# backfin_wifi.net
KiCad netlist of a schematic drawn in EAGLE
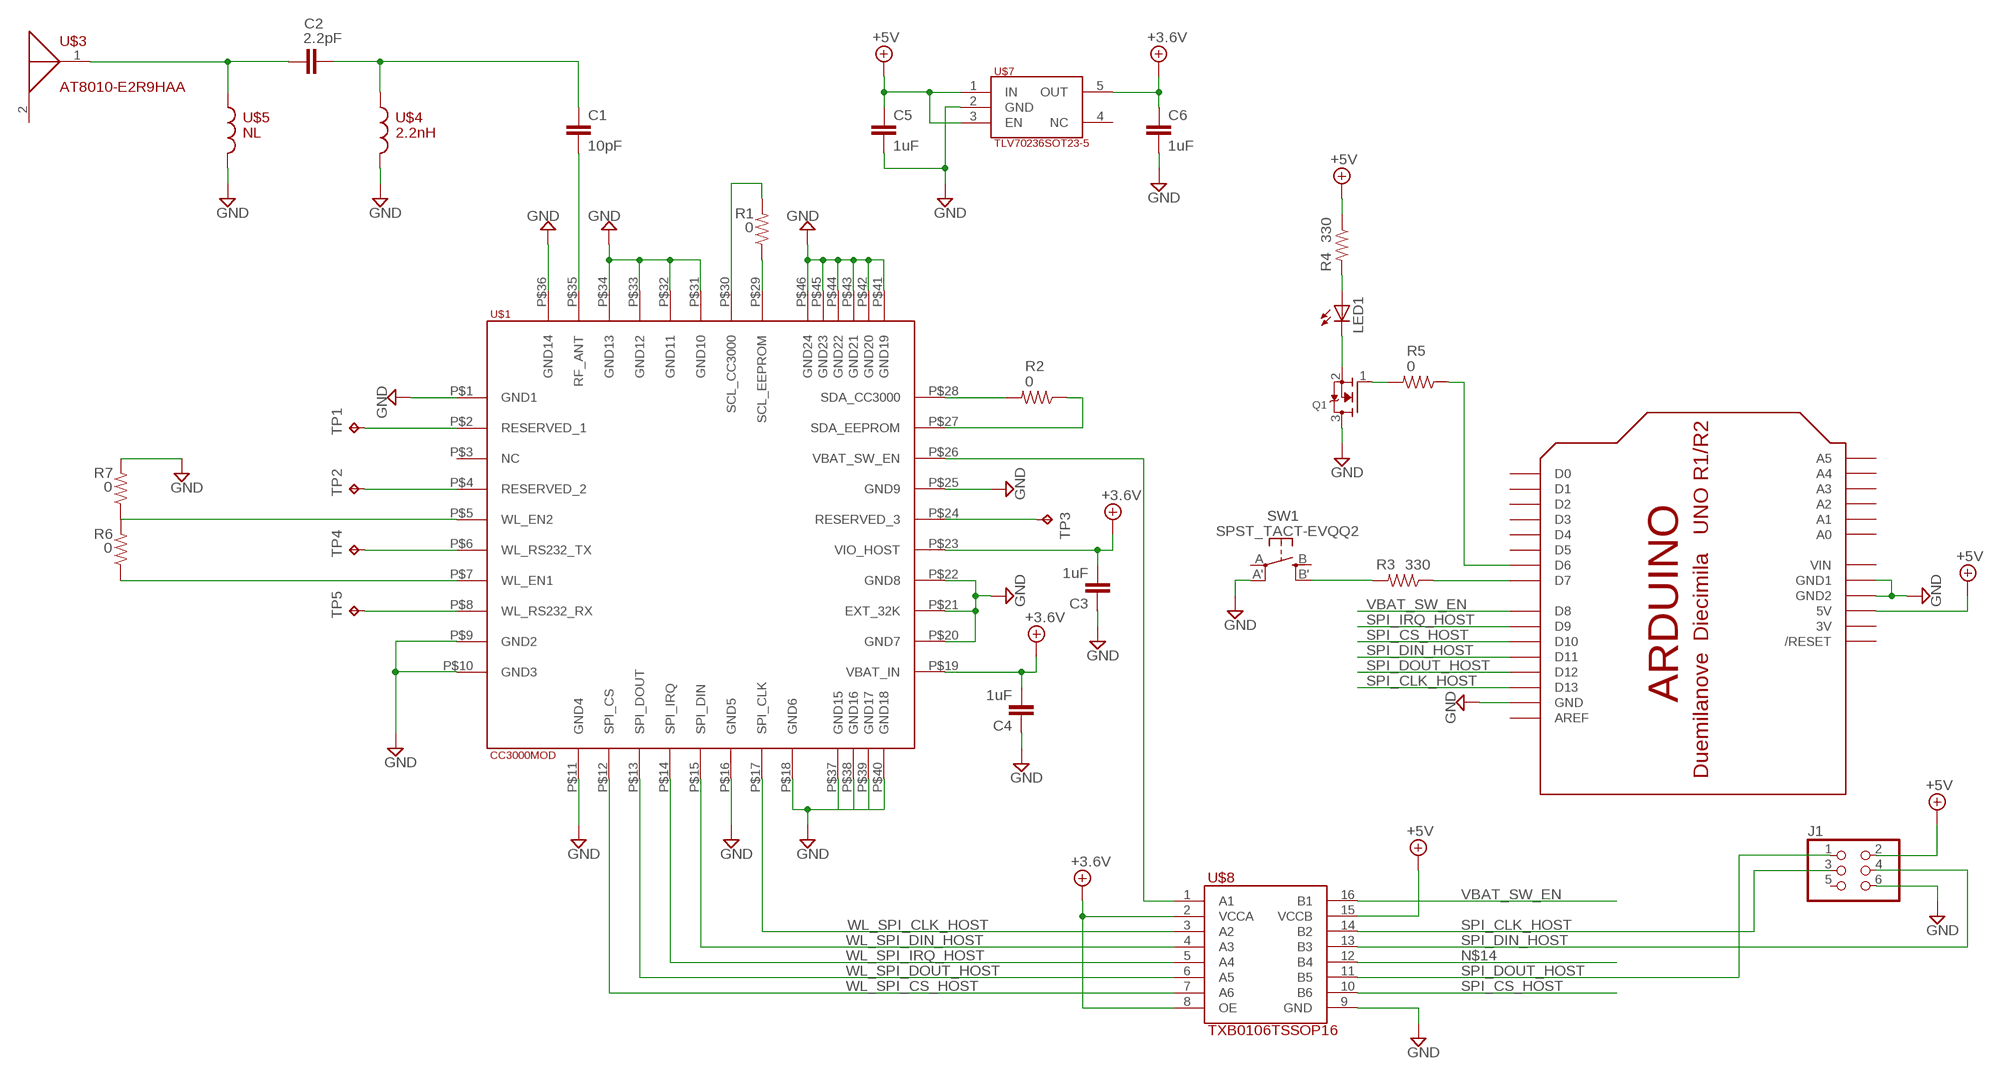
[diagram p0: schematic, sheet 1]

(export (version "E")
  (design (tool "Eeschema 10.0.6"))
  (components
    (comp (ref "C1")
      (value "10pF")
      (footprint "eagle-import:C0402K")
      (libsource (lib "eagle-import") (part "C-EUC0402K"))
    )
    (comp (ref "C2")
      (value "2.2pF")
      (footprint "eagle-import:C0402K")
      (libsource (lib "eagle-import") (part "C-EUC0402K"))
    )
    (comp (ref "C3")
      (value "1uF")
      (footprint "eagle-import:C0402K")
      (libsource (lib "eagle-import") (part "C-EUC0402K"))
    )
    (comp (ref "C4")
      (value "1uF")
      (footprint "eagle-import:C0402K")
      (libsource (lib "eagle-import") (part "C-EUC0402K"))
    )
    (comp (ref "C5")
      (value "1uF")
      (footprint "eagle-import:C0402K")
      (libsource (lib "eagle-import") (part "resistor_C-EUC0402K"))
    )
    (comp (ref "C6")
      (value "1uF")
      (footprint "eagle-import:C0402K")
      (libsource (lib "eagle-import") (part "resistor_C-EUC0402K"))
    )
    (comp (ref "J1")
      (value "PINHD-2X3")
      (footprint "eagle-import:2X03")
      (libsource (lib "eagle-import") (part "PINHD-2X3"))
    )
    (comp (ref "LED1")
      (value "LEDCHIPLED_1206")
      (footprint "eagle-import:CHIPLED_1206")
      (libsource (lib "eagle-import") (part "LEDCHIPLED_1206"))
    )
    (comp (ref "Q1")
      (value "MOSFET-NREFLOW")
      (footprint "eagle-import:SOT23")
      (libsource (lib "eagle-import") (part "MOSFET-NREFLOW"))
    )
    (comp (ref "R1")
      (value "0")
      (footprint "eagle-import:R1005")
      (libsource (lib "eagle-import") (part "R-US_R1005"))
    )
    (comp (ref "R2")
      (value "0")
      (footprint "eagle-import:R1005")
      (libsource (lib "eagle-import") (part "R-US_R1005"))
    )
    (comp (ref "R3")
      (value "330")
      (footprint "eagle-import:R1005")
      (libsource (lib "eagle-import") (part "R-US_R1005"))
    )
    (comp (ref "R4")
      (value "330")
      (footprint "eagle-import:R1005")
      (libsource (lib "eagle-import") (part "R-US_R1005"))
    )
    (comp (ref "R5")
      (value "0")
      (footprint "eagle-import:R1005")
      (libsource (lib "eagle-import") (part "R-US_R1005"))
    )
    (comp (ref "R6")
      (value "0")
      (footprint "eagle-import:R1005")
      (libsource (lib "eagle-import") (part "R-US_R1005"))
    )
    (comp (ref "R7")
      (value "0")
      (footprint "eagle-import:R1005")
      (libsource (lib "eagle-import") (part "R-US_R1005"))
    )
    (comp (ref "SW1")
      (value "SPST_TACT-EVQQ2")
      (footprint "eagle-import:EVQ-Q2")
      (libsource (lib "eagle-import") (part "SPST_TACT-EVQQ2"))
    )
    (comp (ref "TP1")
      (value "TPPAD1-13")
      (footprint "eagle-import:P1-13")
      (libsource (lib "eagle-import") (part "TPPAD1-13"))
    )
    (comp (ref "TP2")
      (value "TPPAD1-13")
      (footprint "eagle-import:P1-13")
      (libsource (lib "eagle-import") (part "TPPAD1-13"))
    )
    (comp (ref "TP3")
      (value "TPPAD1-13")
      (footprint "eagle-import:P1-13")
      (libsource (lib "eagle-import") (part "TPPAD1-13"))
    )
    (comp (ref "TP4")
      (value "TPPAD1-13")
      (footprint "eagle-import:P1-13")
      (libsource (lib "eagle-import") (part "TPPAD1-13"))
    )
    (comp (ref "TP5")
      (value "TPPAD1-13")
      (footprint "eagle-import:P1-13")
      (libsource (lib "eagle-import") (part "TPPAD1-13"))
    )
    (comp (ref "U$1")
      (value "CC3000MOD")
      (footprint "eagle-import:CC3000MOD")
      (libsource (lib "eagle-import") (part "CC3000MOD"))
    )
    (comp (ref "U$2")
      (value "ARDUINOUNO")
      (footprint "eagle-import:ARDUINO")
      (libsource (lib "eagle-import") (part "ARDUINOUNO"))
    )
    (comp (ref "U$3")
      (value "AT8010-E2R9HAA")
      (footprint "eagle-import:AT8010-E2R9HAA")
      (libsource (lib "eagle-import") (part "AT8010-E2R9HAA"))
    )
    (comp (ref "U$4")
      (value "2.2nH")
      (footprint "eagle-import:0402")
      (libsource (lib "eagle-import") (part "INDUCTOR"))
    )
    (comp (ref "U$5")
      (value "NL")
      (footprint "eagle-import:0402")
      (libsource (lib "eagle-import") (part "INDUCTOR"))
    )
    (comp (ref "U$7")
      (value "TLV70236SOT23-5")
      (footprint "eagle-import:SOT23-DBV")
      (libsource (lib "eagle-import") (part "TLV70236SOT23-5"))
    )
    (comp (ref "U$8")
      (value "TXB0106TSSOP16")
      (footprint "eagle-import:TSSOP16")
      (libsource (lib "eagle-import") (part "TXB0106TSSOP16"))
    )
  )
  (nets
    (net (code "1") (name "+3.6V") (class "Default")
      (node (ref "C3") (pin "2") (pinfunction "2_2") (pintype "passive"))
      (node (ref "C4") (pin "2") (pinfunction "2_2") (pintype "passive"))
      (node (ref "C6") (pin "1") (pinfunction "1_1") (pintype "passive"))
      (node (ref "U$1") (pin "P$19") (pinfunction "VBAT_IN_P$19") (pintype "bidirectional"))
      (node (ref "U$1") (pin "P$23") (pinfunction "VIO_HOST_P$23") (pintype "bidirectional"))
      (node (ref "U$7") (pin "5") (pinfunction "OUT_5") (pintype "bidirectional"))
      (node (ref "U$8") (pin "2") (pinfunction "VCCA_2") (pintype "bidirectional"))
      (node (ref "U$8") (pin "8") (pinfunction "OE_8") (pintype "bidirectional"))
    )
    (net (code "2") (name "+5V") (class "Default")
      (node (ref "C5") (pin "1") (pinfunction "1_1") (pintype "passive"))
      (node (ref "J1") (pin "2") (pinfunction "2_2") (pintype "passive"))
      (node (ref "R4") (pin "1") (pinfunction "1_1") (pintype "passive"))
      (node (ref "U$2") (pin "5V") (pinfunction "5V_5V") (pintype "power_in"))
      (node (ref "U$7") (pin "1") (pinfunction "IN_1") (pintype "bidirectional"))
      (node (ref "U$7") (pin "3") (pinfunction "EN_3") (pintype "bidirectional"))
      (node (ref "U$8") (pin "15") (pinfunction "VCCB_15") (pintype "bidirectional"))
    )
    (net (code "3") (name "/3V") (class "Default")
      (node (ref "U$2") (pin "3V") (pinfunction "3V_3V") (pintype "power_in"))
    )
    (net (code "4") (name "/N$14") (class "Default")
      (node (ref "U$8") (pin "12") (pinfunction "B4_12") (pintype "bidirectional"))
    )
    (net (code "5") (name "/SPI_CLK_HOST") (class "Default")
      (node (ref "J1") (pin "3") (pinfunction "3_3") (pintype "passive"))
      (node (ref "U$2") (pin "D13") (pinfunction "D13_D13") (pintype "bidirectional"))
      (node (ref "U$8") (pin "14") (pinfunction "B2_14") (pintype "bidirectional"))
    )
    (net (code "6") (name "/SPI_CS_HOST") (class "Default")
      (node (ref "U$2") (pin "D10") (pinfunction "D10_D10") (pintype "bidirectional"))
      (node (ref "U$8") (pin "10") (pinfunction "B6_10") (pintype "bidirectional"))
    )
    (net (code "7") (name "/SPI_DIN_HOST") (class "Default")
      (node (ref "J1") (pin "4") (pinfunction "4_4") (pintype "passive"))
      (node (ref "U$2") (pin "D11") (pinfunction "D11_D11") (pintype "bidirectional"))
      (node (ref "U$8") (pin "13") (pinfunction "B3_13") (pintype "bidirectional"))
    )
    (net (code "8") (name "/SPI_DOUT_HOST") (class "Default")
      (node (ref "J1") (pin "1") (pinfunction "1_1") (pintype "passive"))
      (node (ref "U$2") (pin "D12") (pinfunction "D12_D12") (pintype "bidirectional"))
      (node (ref "U$8") (pin "11") (pinfunction "B5_11") (pintype "bidirectional"))
    )
    (net (code "9") (name "/SPI_IRQ_HOST") (class "Default")
      (node (ref "U$2") (pin "D9") (pinfunction "D9_D9") (pintype "bidirectional"))
    )
    (net (code "10") (name "/VBAT_SW_EN") (class "Default")
      (node (ref "U$2") (pin "D8") (pinfunction "D8_D8") (pintype "bidirectional"))
      (node (ref "U$8") (pin "16") (pinfunction "B1_16") (pintype "bidirectional"))
    )
    (net (code "11") (name "/VIN") (class "Default")
      (node (ref "U$2") (pin "VIN") (pinfunction "VIN_VIN") (pintype "power_in"))
    )
    (net (code "12") (name "/WL_SPI_CLK_HOST") (class "Default")
      (node (ref "U$1") (pin "P$17") (pinfunction "SPI_CLK_P$17") (pintype "bidirectional"))
      (node (ref "U$8") (pin "3") (pinfunction "A2_3") (pintype "bidirectional"))
    )
    (net (code "13") (name "/WL_SPI_CS_HOST") (class "Default")
      (node (ref "U$1") (pin "P$12") (pinfunction "SPI_CS_P$12") (pintype "bidirectional"))
      (node (ref "U$8") (pin "7") (pinfunction "A6_7") (pintype "bidirectional"))
    )
    (net (code "14") (name "/WL_SPI_DIN_HOST") (class "Default")
      (node (ref "U$1") (pin "P$15") (pinfunction "SPI_DIN_P$15") (pintype "bidirectional"))
      (node (ref "U$8") (pin "4") (pinfunction "A3_4") (pintype "bidirectional"))
    )
    (net (code "15") (name "/WL_SPI_DOUT_HOST") (class "Default")
      (node (ref "U$1") (pin "P$13") (pinfunction "SPI_DOUT_P$13") (pintype "bidirectional"))
      (node (ref "U$8") (pin "6") (pinfunction "A5_6") (pintype "bidirectional"))
    )
    (net (code "16") (name "/WL_SPI_IRQ_HOST") (class "Default")
      (node (ref "U$1") (pin "P$14") (pinfunction "SPI_IRQ_P$14") (pintype "bidirectional"))
      (node (ref "U$8") (pin "5") (pinfunction "A4_5") (pintype "bidirectional"))
    )
    (net (code "17") (name "GND") (class "Default")
      (node (ref "C3") (pin "1") (pinfunction "1_1") (pintype "passive"))
      (node (ref "C4") (pin "1") (pinfunction "1_1") (pintype "passive"))
      (node (ref "C5") (pin "2") (pinfunction "2_2") (pintype "passive"))
      (node (ref "C6") (pin "2") (pinfunction "2_2") (pintype "passive"))
      (node (ref "J1") (pin "6") (pinfunction "6_6") (pintype "passive"))
      (node (ref "Q1") (pin "3") (pinfunction "D_3") (pintype "bidirectional"))
      (node (ref "R7") (pin "2") (pinfunction "2_2") (pintype "passive"))
      (node (ref "SW1") (pin "A'") (pinfunction "P1_A'") (pintype "passive"))
      (node (ref "U$1") (pin "P$1") (pinfunction "GND1_P$1") (pintype "bidirectional"))
      (node (ref "U$1") (pin "P$10") (pinfunction "GND3_P$10") (pintype "bidirectional"))
      (node (ref "U$1") (pin "P$11") (pinfunction "GND4_P$11") (pintype "bidirectional"))
      (node (ref "U$1") (pin "P$16") (pinfunction "GND5_P$16") (pintype "bidirectional"))
      (node (ref "U$1") (pin "P$18") (pinfunction "GND6_P$18") (pintype "bidirectional"))
      (node (ref "U$1") (pin "P$20") (pinfunction "GND7_P$20") (pintype "bidirectional"))
      (node (ref "U$1") (pin "P$21") (pinfunction "EXT_32K_P$21") (pintype "bidirectional"))
      (node (ref "U$1") (pin "P$22") (pinfunction "GND8_P$22") (pintype "bidirectional"))
      (node (ref "U$1") (pin "P$25") (pinfunction "GND9_P$25") (pintype "bidirectional"))
      (node (ref "U$1") (pin "P$31") (pinfunction "GND10_P$31") (pintype "bidirectional"))
      (node (ref "U$1") (pin "P$32") (pinfunction "GND11_P$32") (pintype "bidirectional"))
      (node (ref "U$1") (pin "P$33") (pinfunction "GND12_P$33") (pintype "bidirectional"))
      (node (ref "U$1") (pin "P$34") (pinfunction "GND13_P$34") (pintype "bidirectional"))
      (node (ref "U$1") (pin "P$36") (pinfunction "GND14_P$36") (pintype "bidirectional"))
      (node (ref "U$1") (pin "P$37") (pinfunction "GND15_P$37") (pintype "bidirectional"))
      (node (ref "U$1") (pin "P$38") (pinfunction "GND16_P$38") (pintype "bidirectional"))
      (node (ref "U$1") (pin "P$39") (pinfunction "GND17_P$39") (pintype "bidirectional"))
      (node (ref "U$1") (pin "P$40") (pinfunction "GND18_P$40") (pintype "bidirectional"))
      (node (ref "U$1") (pin "P$41") (pinfunction "GND19_P$41") (pintype "bidirectional"))
      (node (ref "U$1") (pin "P$42") (pinfunction "GND20_P$42") (pintype "bidirectional"))
      (node (ref "U$1") (pin "P$43") (pinfunction "GND21_P$43") (pintype "bidirectional"))
      (node (ref "U$1") (pin "P$44") (pinfunction "GND22_P$44") (pintype "bidirectional"))
      (node (ref "U$1") (pin "P$45") (pinfunction "GND23_P$45") (pintype "bidirectional"))
      (node (ref "U$1") (pin "P$46") (pinfunction "GND24_P$46") (pintype "bidirectional"))
      (node (ref "U$1") (pin "P$9") (pinfunction "GND2_P$9") (pintype "bidirectional"))
      (node (ref "U$2") (pin "GND") (pinfunction "GND_GND") (pintype "power_in"))
      (node (ref "U$2") (pin "GND1") (pinfunction "GND1_GND1") (pintype "power_in"))
      (node (ref "U$2") (pin "GND2") (pinfunction "GND2_GND2") (pintype "power_in"))
      (node (ref "U$4") (pin "2") (pinfunction "2_2") (pintype "bidirectional"))
      (node (ref "U$5") (pin "2") (pinfunction "2_2") (pintype "bidirectional"))
      (node (ref "U$7") (pin "2") (pinfunction "GND_2") (pintype "bidirectional"))
      (node (ref "U$8") (pin "9") (pinfunction "GND_9") (pintype "bidirectional"))
    )
    (net (code "18") (name "Net-(C1-Pad1)") (class "Default")
      (node (ref "C1") (pin "1") (pinfunction "1_1") (pintype "passive"))
      (node (ref "C2") (pin "2") (pinfunction "2_2") (pintype "passive"))
      (node (ref "U$4") (pin "1") (pinfunction "1_1") (pintype "bidirectional"))
    )
    (net (code "19") (name "Net-(LED1-PadA)") (class "Default")
      (node (ref "LED1") (pin "A") (pinfunction "A_A") (pintype "passive"))
      (node (ref "R4") (pin "2") (pinfunction "2_2") (pintype "passive"))
    )
    (net (code "20") (name "Net-(Q1-G)") (class "Default")
      (node (ref "Q1") (pin "1") (pinfunction "G_1") (pintype "bidirectional"))
      (node (ref "R5") (pin "2") (pinfunction "2_2") (pintype "passive"))
    )
    (net (code "21") (name "Net-(Q1-S)") (class "Default")
      (node (ref "LED1") (pin "C") (pinfunction "C_C") (pintype "passive"))
      (node (ref "Q1") (pin "2") (pinfunction "S_2") (pintype "bidirectional"))
    )
    (net (code "22") (name "Net-(R3-Pad1)") (class "Default")
      (node (ref "R3") (pin "1") (pinfunction "1_1") (pintype "passive"))
      (node (ref "U$2") (pin "D7") (pinfunction "D7_D7") (pintype "bidirectional"))
    )
    (net (code "23") (name "Net-(R5-Pad1)") (class "Default")
      (node (ref "R5") (pin "1") (pinfunction "1_1") (pintype "passive"))
      (node (ref "U$2") (pin "D6") (pinfunction "D6_D6") (pintype "bidirectional"))
    )
    (net (code "24") (name "Net-(SW1-S1)") (class "Default")
      (node (ref "R3") (pin "2") (pinfunction "2_2") (pintype "passive"))
      (node (ref "SW1") (pin "B'") (pinfunction "S1_B'") (pintype "passive"))
    )
    (net (code "25") (name "Net-(U$1-RESERVED_1)") (class "Default")
      (node (ref "TP1") (pin "TP") (pinfunction "TP_TP") (pintype "input"))
      (node (ref "U$1") (pin "P$2") (pinfunction "RESERVED_1_P$2") (pintype "bidirectional"))
    )
    (net (code "26") (name "Net-(U$1-RESERVED_2)") (class "Default")
      (node (ref "TP2") (pin "TP") (pinfunction "TP_TP") (pintype "input"))
      (node (ref "U$1") (pin "P$4") (pinfunction "RESERVED_2_P$4") (pintype "bidirectional"))
    )
    (net (code "27") (name "Net-(U$1-RESERVED_3)") (class "Default")
      (node (ref "TP3") (pin "TP") (pinfunction "TP_TP") (pintype "input"))
      (node (ref "U$1") (pin "P$24") (pinfunction "RESERVED_3_P$24") (pintype "bidirectional"))
    )
    (net (code "28") (name "Net-(U$1-RF_ANT)") (class "Default")
      (node (ref "C1") (pin "2") (pinfunction "2_2") (pintype "passive"))
      (node (ref "U$1") (pin "P$35") (pinfunction "RF_ANT_P$35") (pintype "bidirectional"))
    )
    (net (code "29") (name "Net-(U$1-SCL_CC3000)") (class "Default")
      (node (ref "R1") (pin "2") (pinfunction "2_2") (pintype "passive"))
      (node (ref "U$1") (pin "P$30") (pinfunction "SCL_CC3000_P$30") (pintype "bidirectional"))
    )
    (net (code "30") (name "Net-(U$1-SCL_EEPROM)") (class "Default")
      (node (ref "R1") (pin "1") (pinfunction "1_1") (pintype "passive"))
      (node (ref "U$1") (pin "P$29") (pinfunction "SCL_EEPROM_P$29") (pintype "bidirectional"))
    )
    (net (code "31") (name "Net-(U$1-SDA_CC3000)") (class "Default")
      (node (ref "R2") (pin "2") (pinfunction "2_2") (pintype "passive"))
      (node (ref "U$1") (pin "P$28") (pinfunction "SDA_CC3000_P$28") (pintype "bidirectional"))
    )
    (net (code "32") (name "Net-(U$1-SDA_EEPROM)") (class "Default")
      (node (ref "R2") (pin "1") (pinfunction "1_1") (pintype "passive"))
      (node (ref "U$1") (pin "P$27") (pinfunction "SDA_EEPROM_P$27") (pintype "bidirectional"))
    )
    (net (code "33") (name "Net-(U$1-VBAT_SW_EN)") (class "Default")
      (node (ref "U$1") (pin "P$26") (pinfunction "VBAT_SW_EN_P$26") (pintype "bidirectional"))
      (node (ref "U$8") (pin "1") (pinfunction "A1_1") (pintype "bidirectional"))
    )
    (net (code "34") (name "Net-(U$1-WL_EN1)") (class "Default")
      (node (ref "R6") (pin "1") (pinfunction "1_1") (pintype "passive"))
      (node (ref "U$1") (pin "P$7") (pinfunction "WL_EN1_P$7") (pintype "bidirectional"))
    )
    (net (code "35") (name "Net-(U$1-WL_EN2)") (class "Default")
      (node (ref "R6") (pin "2") (pinfunction "2_2") (pintype "passive"))
      (node (ref "R7") (pin "1") (pinfunction "1_1") (pintype "passive"))
      (node (ref "U$1") (pin "P$5") (pinfunction "WL_EN2_P$5") (pintype "bidirectional"))
    )
    (net (code "36") (name "Net-(U$1-WL_RS232_RX)") (class "Default")
      (node (ref "TP5") (pin "TP") (pinfunction "TP_TP") (pintype "input"))
      (node (ref "U$1") (pin "P$8") (pinfunction "WL_RS232_RX_P$8") (pintype "bidirectional"))
    )
    (net (code "37") (name "Net-(U$1-WL_RS232_TX)") (class "Default")
      (node (ref "TP4") (pin "TP") (pinfunction "TP_TP") (pintype "input"))
      (node (ref "U$1") (pin "P$6") (pinfunction "WL_RS232_TX_P$6") (pintype "bidirectional"))
    )
    (net (code "38") (name "Net-(U$3-FEED)") (class "Default")
      (node (ref "C2") (pin "1") (pinfunction "1_1") (pintype "passive"))
      (node (ref "U$3") (pin "1") (pinfunction "FEED_1") (pintype "bidirectional"))
      (node (ref "U$5") (pin "1") (pinfunction "1_1") (pintype "bidirectional"))
    )
    (net (code "39") (name "unconnected-(J1-Pad5)") (class "Default")
      (node (ref "J1") (pin "5") (pinfunction "5_5") (pintype "passive"))
    )
    (net (code "40") (name "unconnected-(SW1-P-PadA)") (class "Default")
      (node (ref "SW1") (pin "A") (pinfunction "P_A") (pintype "passive"))
    )
    (net (code "41") (name "unconnected-(SW1-S-PadB)") (class "Default")
      (node (ref "SW1") (pin "B") (pinfunction "S_B") (pintype "passive"))
    )
    (net (code "42") (name "unconnected-(U$1-NC-PadP$3)") (class "Default")
      (node (ref "U$1") (pin "P$3") (pinfunction "NC_P$3") (pintype "bidirectional"))
    )
    (net (code "43") (name "unconnected-(U$2-PadA0)") (class "Default")
      (node (ref "U$2") (pin "A0") (pinfunction "A0_A0") (pintype "bidirectional"))
    )
    (net (code "44") (name "unconnected-(U$2-PadA1)") (class "Default")
      (node (ref "U$2") (pin "A1") (pinfunction "A1_A1") (pintype "bidirectional"))
    )
    (net (code "45") (name "unconnected-(U$2-PadA2)") (class "Default")
      (node (ref "U$2") (pin "A2") (pinfunction "A2_A2") (pintype "bidirectional"))
    )
    (net (code "46") (name "unconnected-(U$2-PadA3)") (class "Default")
      (node (ref "U$2") (pin "A3") (pinfunction "A3_A3") (pintype "bidirectional"))
    )
    (net (code "47") (name "unconnected-(U$2-PadA4)") (class "Default")
      (node (ref "U$2") (pin "A4") (pinfunction "A4_A4") (pintype "bidirectional"))
    )
    (net (code "48") (name "unconnected-(U$2-PadA5)") (class "Default")
      (node (ref "U$2") (pin "A5") (pinfunction "A5_A5") (pintype "bidirectional"))
    )
    (net (code "49") (name "unconnected-(U$2-PadAREF)") (class "Default")
      (node (ref "U$2") (pin "AREF") (pinfunction "AREF_AREF") (pintype "bidirectional"))
    )
    (net (code "50") (name "unconnected-(U$2-PadD0)") (class "Default")
      (node (ref "U$2") (pin "D0") (pinfunction "D0_D0") (pintype "bidirectional"))
    )
    (net (code "51") (name "unconnected-(U$2-PadD1)") (class "Default")
      (node (ref "U$2") (pin "D1") (pinfunction "D1_D1") (pintype "bidirectional"))
    )
    (net (code "52") (name "unconnected-(U$2-PadD2)") (class "Default")
      (node (ref "U$2") (pin "D2") (pinfunction "D2_D2") (pintype "bidirectional"))
    )
    (net (code "53") (name "unconnected-(U$2-PadD3)") (class "Default")
      (node (ref "U$2") (pin "D3") (pinfunction "D3_D3") (pintype "bidirectional"))
    )
    (net (code "54") (name "unconnected-(U$2-PadD4)") (class "Default")
      (node (ref "U$2") (pin "D4") (pinfunction "D4_D4") (pintype "bidirectional"))
    )
    (net (code "55") (name "unconnected-(U$2-PadD5)") (class "Default")
      (node (ref "U$2") (pin "D5") (pinfunction "D5_D5") (pintype "bidirectional"))
    )
    (net (code "56") (name "unconnected-(U$2-{slash}RESET-PadRESET)") (class "Default")
      (node (ref "U$2") (pin "RESET") (pinfunction "/RESET_RESET") (pintype "bidirectional"))
    )
    (net (code "57") (name "unconnected-(U$3-NC-Pad2)") (class "Default")
      (node (ref "U$3") (pin "2") (pinfunction "NC_2") (pintype "bidirectional"))
    )
    (net (code "58") (name "unconnected-(U$7-NC-Pad4)") (class "Default")
      (node (ref "U$7") (pin "4") (pinfunction "NC_4") (pintype "bidirectional"))
    )
  )
)
